# wristband-pcb.net
KiCad netlist of a schematic drawn in EAGLE
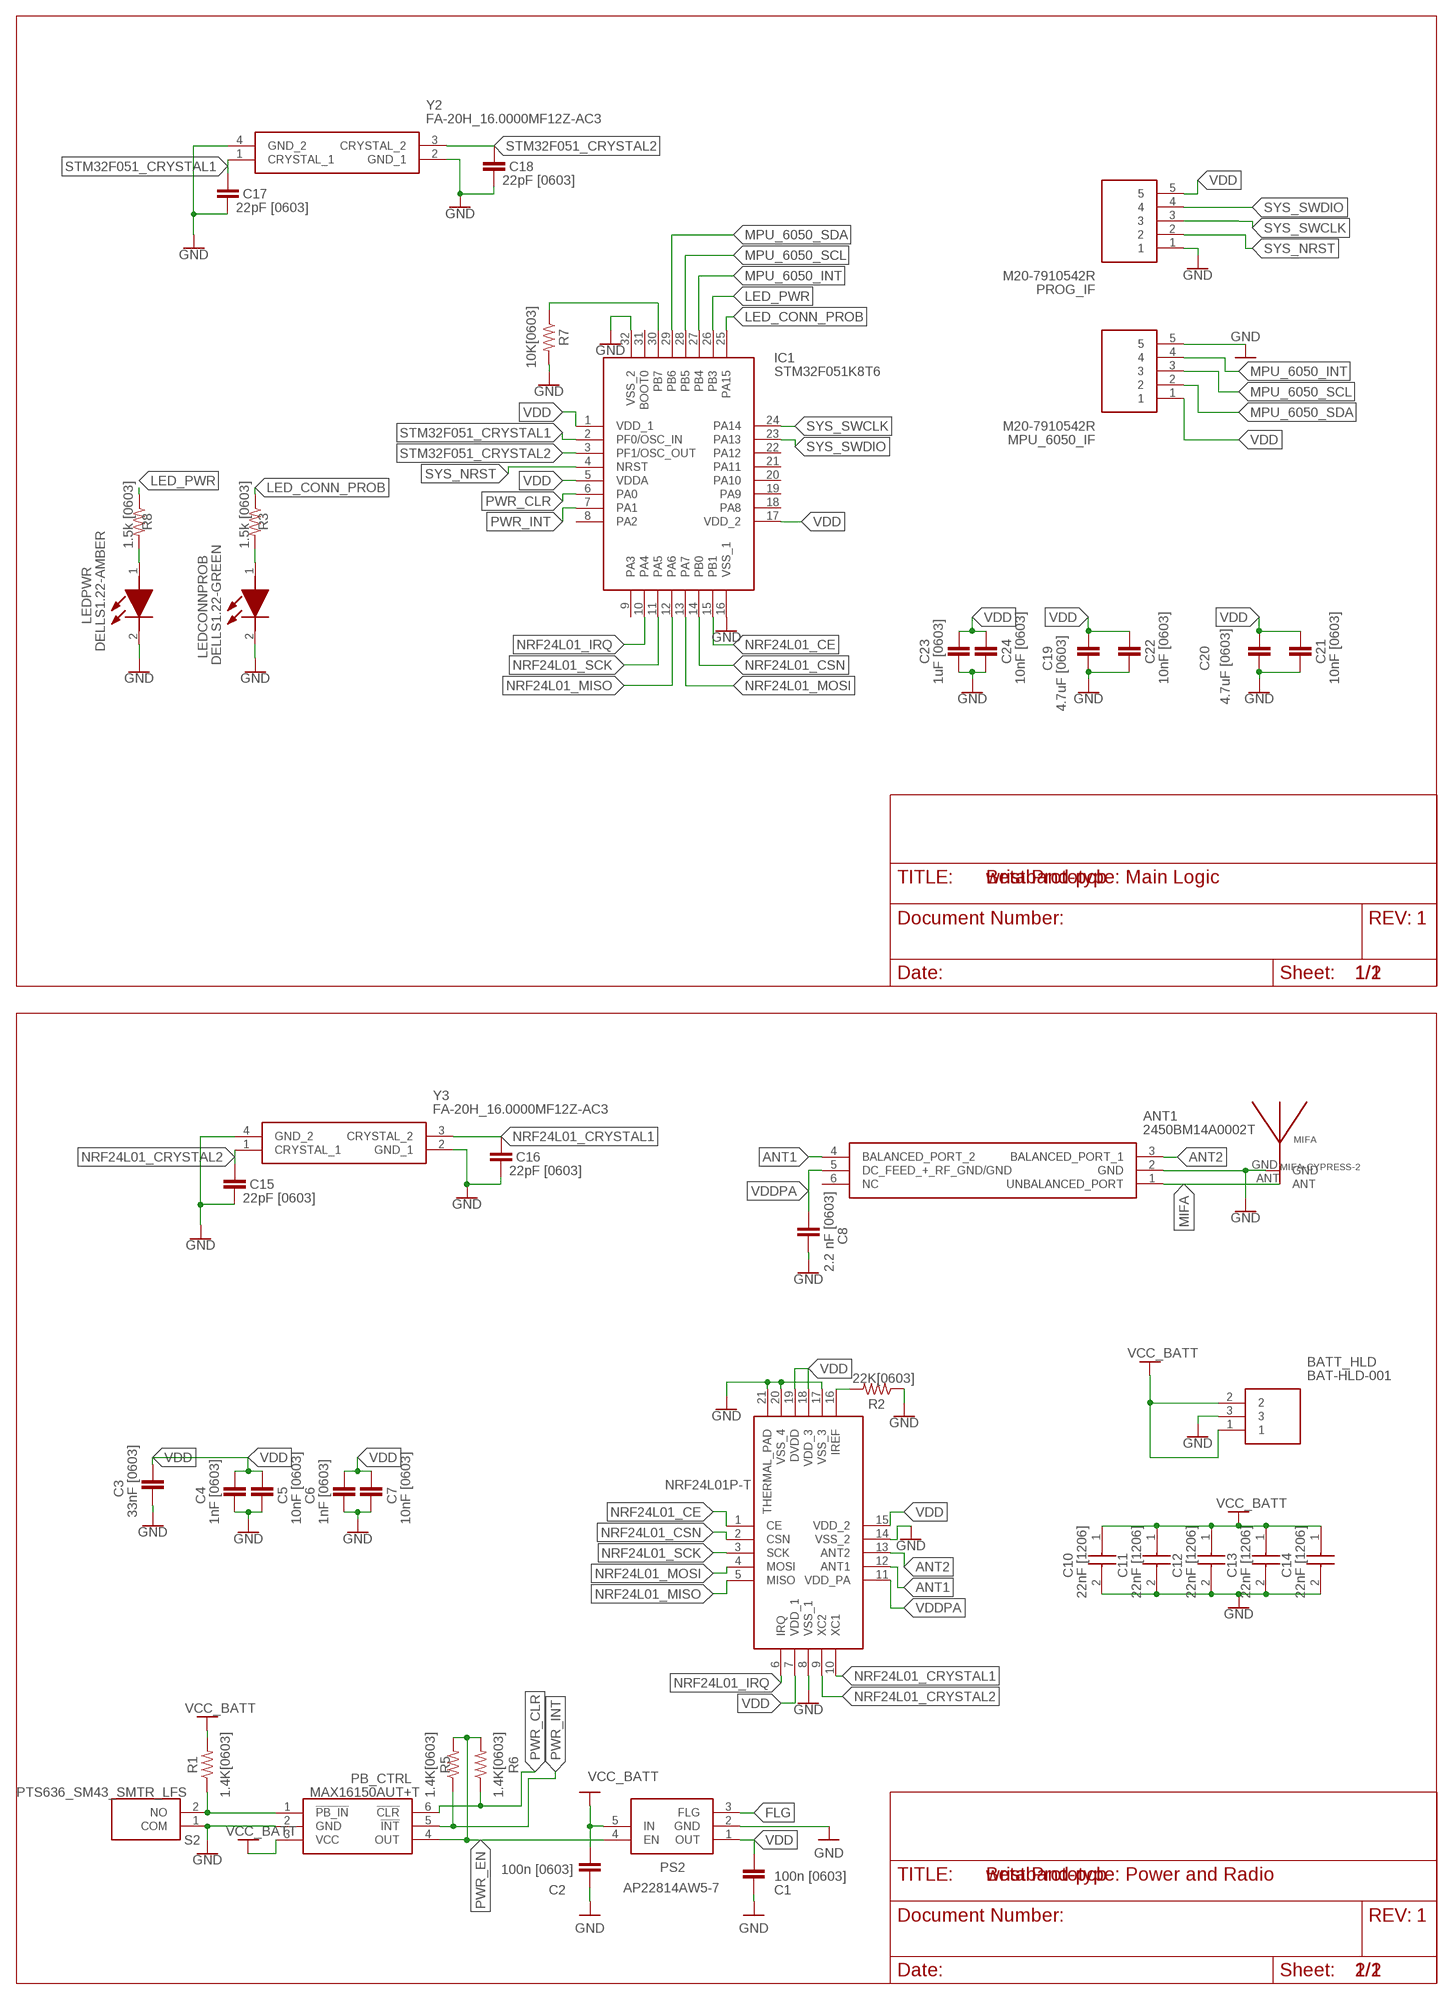
[diagram p0: schematic, sheet 1]

(export (version "E")
  (design (tool "Eeschema 10.0.6"))
  (components
    (comp (ref "ANT1")
      (value "2450BM14A0002T")
      (footprint "eagle-import:2450BM14A0002T")
      (fields (field (name "MOUSER_PART_NUMBER") "609-2450BM14A0002T"))
      (libsource (lib "eagle-import") (part "2450BM14A0002T"))
    )
    (comp (ref "BATT_HLD")
      (value "BAT-HLD-001")
      (footprint "eagle-import:BATHLD001")
      (fields (field (name "MOUSER_PART_NUMBER") "712-BAT-HLD-001"))
      (libsource (lib "eagle-import") (part "BAT-HLD-001"))
    )
    (comp (ref "C1")
      (value "100n [0603]")
      (footprint "eagle-import:CAPC1608X85")
      (libsource (lib "eagle-import") (part "CCHIP-0603(1608-METRIC)_"))
    )
    (comp (ref "C2")
      (value "100n [0603]")
      (footprint "eagle-import:CAPC1608X85")
      (libsource (lib "eagle-import") (part "CCHIP-0603(1608-METRIC)_"))
    )
    (comp (ref "C3")
      (value "33nF [0603]")
      (footprint "eagle-import:RESC0603_L")
      (libsource (lib "eagle-import") (part "CAPACITOR_0603_L"))
    )
    (comp (ref "C4")
      (value "1nF [0603]")
      (footprint "eagle-import:RESC0603_L")
      (libsource (lib "eagle-import") (part "CAPACITOR_0603_L"))
    )
    (comp (ref "C5")
      (value "10nF [0603]")
      (footprint "eagle-import:RESC0603_L")
      (libsource (lib "eagle-import") (part "CAPACITOR_0603_L"))
    )
    (comp (ref "C6")
      (value "1nF [0603]")
      (footprint "eagle-import:RESC0603_L")
      (libsource (lib "eagle-import") (part "CAPACITOR_0603_L"))
    )
    (comp (ref "C7")
      (value "10nF [0603]")
      (footprint "eagle-import:RESC0603_L")
      (libsource (lib "eagle-import") (part "CAPACITOR_0603_L"))
    )
    (comp (ref "C8")
      (value "2.2 nF [0603]")
      (footprint "eagle-import:RESC0603_L")
      (libsource (lib "eagle-import") (part "CAPACITOR_0603_L"))
    )
    (comp (ref "C10")
      (value "22nF [1206]")
      (footprint "eagle-import:CAPC3216X180N")
      (fields (field (name "MANUFACTURER_PART_NUMBER") "CL31B226KPHNNNE"))
      (libsource (lib "eagle-import") (part "CL31B226KPHNNNE"))
    )
    (comp (ref "C11")
      (value "22nF [1206]")
      (footprint "eagle-import:CAPC3216X180N")
      (fields (field (name "MANUFACTURER_PART_NUMBER") "CL31B226KPHNNNE"))
      (libsource (lib "eagle-import") (part "CL31B226KPHNNNE"))
    )
    (comp (ref "C12")
      (value "22nF [1206]")
      (footprint "eagle-import:CAPC3216X180N")
      (fields (field (name "MANUFACTURER_PART_NUMBER") "CL31B226KPHNNNE"))
      (libsource (lib "eagle-import") (part "CL31B226KPHNNNE"))
    )
    (comp (ref "C13")
      (value "22nF [1206]")
      (footprint "eagle-import:CAPC3216X180N")
      (fields (field (name "MANUFACTURER_PART_NUMBER") "CL31B226KPHNNNE"))
      (libsource (lib "eagle-import") (part "CL31B226KPHNNNE"))
    )
    (comp (ref "C14")
      (value "22nF [1206]")
      (footprint "eagle-import:CAPC3216X180N")
      (fields (field (name "MANUFACTURER_PART_NUMBER") "CL31B226KPHNNNE"))
      (libsource (lib "eagle-import") (part "CL31B226KPHNNNE"))
    )
    (comp (ref "C15")
      (value "22pF [0603]")
      (footprint "eagle-import:RESC0603_L")
      (libsource (lib "eagle-import") (part "CAPACITOR_0603_L"))
    )
    (comp (ref "C16")
      (value "22pF [0603]")
      (footprint "eagle-import:RESC0603_L")
      (libsource (lib "eagle-import") (part "CAPACITOR_0603_L"))
    )
    (comp (ref "C17")
      (value "22pF [0603]")
      (footprint "eagle-import:RESC0603_L")
      (libsource (lib "eagle-import") (part "CAPACITOR_0603_L"))
    )
    (comp (ref "C18")
      (value "22pF [0603]")
      (footprint "eagle-import:RESC0603_L")
      (libsource (lib "eagle-import") (part "CAPACITOR_0603_L"))
    )
    (comp (ref "C19")
      (value "4.7uF [0603]")
      (footprint "eagle-import:RESC0603_L")
      (libsource (lib "eagle-import") (part "CAPACITOR_0603_L"))
    )
    (comp (ref "C20")
      (value "4.7uF [0603]")
      (footprint "eagle-import:RESC0603_L")
      (libsource (lib "eagle-import") (part "CAPACITOR_0603_L"))
    )
    (comp (ref "C21")
      (value "10nF [0603]")
      (footprint "eagle-import:RESC0603_L")
      (libsource (lib "eagle-import") (part "CAPACITOR_0603_L"))
    )
    (comp (ref "C22")
      (value "10nF [0603]")
      (footprint "eagle-import:RESC0603_L")
      (libsource (lib "eagle-import") (part "CAPACITOR_0603_L"))
    )
    (comp (ref "C23")
      (value "1uF [0603]")
      (footprint "eagle-import:RESC0603_L")
      (libsource (lib "eagle-import") (part "CAPACITOR_0603_L"))
    )
    (comp (ref "C24")
      (value "10nF [0603]")
      (footprint "eagle-import:RESC0603_L")
      (libsource (lib "eagle-import") (part "CAPACITOR_0603_L"))
    )
    (comp (ref "IC1")
      (value "STM32F051K8T6")
      (footprint "eagle-import:QFP80P900X900X160-32N")
      (fields (field (name "MOUSER_PART_NUMBER") "511-STM32F051K8T6"))
      (libsource (lib "eagle-import") (part "STM32F051K8T6"))
    )
    (comp (ref "LEDCONNPROB")
      (value "DELLS1.22-GREEN")
      (footprint "eagle-import:KSDELLS122JHKI1")
      (fields
        (field (name "MANUFACTURER_PART_NUMBER") "KS DELLS1.22-JHKI-1")
        (field (name "MOUSER_PART_NUMBER") "720-KSDELLS122A4852")
      )
      (libsource (lib "eagle-import") (part "KS_DELLS1.22-JHKI-1"))
    )
    (comp (ref "LEDPWR")
      (value "DELLS1.22-AMBER")
      (footprint "eagle-import:KSDELLS122JHKI1")
      (fields
        (field (name "MANUFACTURER_PART_NUMBER") "KS DELLS1.22-JHKI-1")
        (field (name "MOUSER_PART_NUMBER") "720-KSDELLS122A4852")
      )
      (libsource (lib "eagle-import") (part "KS_DELLS1.22-JHKI-1"))
    )
    (comp (ref "MIFA")
      (value "MIFA-CYPRESS-2")
      (footprint "eagle-import:MIFA-CYPRESS-2")
      (libsource (lib "eagle-import") (part "MIFA-CYPRESS-2"))
    )
    (comp (ref "MPU_6050_IF")
      (value "M20-7910542R")
      (footprint "eagle-import:M207910542R")
      (fields (field (name "MOUSER_PART_NUMBER") "855-M20-7910542R"))
      (libsource (lib "eagle-import") (part "M20-7910542R"))
    )
    (comp (ref "NRF24L01+")
      (value "NRF24L01P-T")
      (footprint "eagle-import:QFN50P400X400X95-21N")
      (fields
        (field (name "MANUFACTURER_PART_NUMBER") "nRF24L01P-T")
        (field (name "MOUSER_PART_NUMBER") "949-NRF24L01P-T")
      )
      (libsource (lib "eagle-import") (part "NRF24L01P-T"))
    )
    (comp (ref "PB_CTRL")
      (value "MAX16150AUT+T")
      (footprint "eagle-import:SOT95P280X145-6N")
      (fields (field (name "MOUSER_PART_NUMBER") "700-MAX16150AUT+T"))
      (libsource (lib "eagle-import") (part "MAX16150AUT+T"))
    )
    (comp (ref "PROG_IF")
      (value "M20-7910542R")
      (footprint "eagle-import:M207910542R")
      (fields (field (name "MOUSER_PART_NUMBER") "855-M20-7910542R"))
      (libsource (lib "eagle-import") (part "M20-7910542R"))
    )
    (comp (ref "PS2")
      (value "AP22814AW5-7")
      (footprint "eagle-import:SOT95P285X130-5N")
      (fields (field (name "MOUSER_PART_NUMBER") "621-AP22814AW5-7"))
      (libsource (lib "eagle-import") (part "AP22814AW5-7"))
    )
    (comp (ref "R1")
      (value "1.4K[0603]")
      (footprint "eagle-import:RESC1608X60")
      (libsource (lib "eagle-import") (part "R-USCHIP-0603(1608-METRIC)_"))
    )
    (comp (ref "R2")
      (value "22K[0603]")
      (footprint "eagle-import:RESC1608X60")
      (libsource (lib "eagle-import") (part "R-USCHIP-0603(1608-METRIC)_"))
    )
    (comp (ref "R3")
      (value "1.5k [0603]")
      (footprint "eagle-import:RESC1608X60")
      (libsource (lib "eagle-import") (part "R-USCHIP-0603(1608-METRIC)_"))
    )
    (comp (ref "R5")
      (value "1.4K[0603]")
      (footprint "eagle-import:RESC1608X60")
      (libsource (lib "eagle-import") (part "R-USCHIP-0603(1608-METRIC)_"))
    )
    (comp (ref "R6")
      (value "1.4K[0603]")
      (footprint "eagle-import:RESC1608X60")
      (libsource (lib "eagle-import") (part "R-USCHIP-0603(1608-METRIC)_"))
    )
    (comp (ref "R7")
      (value "10K[0603]")
      (footprint "eagle-import:RESC1608X60")
      (libsource (lib "eagle-import") (part "R-USCHIP-0603(1608-METRIC)_"))
    )
    (comp (ref "R8")
      (value "1.5k [0603]")
      (footprint "eagle-import:RESC1608X60")
      (libsource (lib "eagle-import") (part "R-USCHIP-0603(1608-METRIC)_"))
    )
    (comp (ref "S2")
      (value "PTS636_SM43_SMTR_LFS")
      (footprint "eagle-import:PTS636SM43SMTRLFS")
      (fields
        (field (name "MANUFACTURER_PART_NUMBER") "PTS636 SM43 SMTR LFS")
        (field (name "MOUSER_PART_NUMBER") "611-PTS636SM43SMTRLF")
      )
      (libsource (lib "eagle-import") (part "PTS636_SM43_SMTR_LFS"))
    )
    (comp (ref "Y2")
      (value "FA-20H_16.0000MF12Z-AC3")
      (footprint "eagle-import:FA20H160000MF12ZAC3")
      (fields
        (field (name "MANUFACTURER_PART_NUMBER") "FA-20H 16.0000MF12Z-AC3")
        (field (name "MOUSER_PART_NUMBER") "732-FA20H-16F12Z-AC3")
      )
      (libsource (lib "eagle-import") (part "FA-20H_16.0000MF12Z-AC3"))
    )
    (comp (ref "Y3")
      (value "FA-20H_16.0000MF12Z-AC3")
      (footprint "eagle-import:FA20H160000MF12ZAC3")
      (fields
        (field (name "MANUFACTURER_PART_NUMBER") "FA-20H 16.0000MF12Z-AC3")
        (field (name "MOUSER_PART_NUMBER") "732-FA20H-16F12Z-AC3")
      )
      (libsource (lib "eagle-import") (part "FA-20H_16.0000MF12Z-AC3"))
    )
  )
  (nets
    (net (code "1") (name "ANT1") (class "Default")
      (node (ref "ANT1") (pin "4") (pinfunction "BALANCED_PORT_2_4") (pintype "bidirectional"))
      (node (ref "NRF24L01+") (pin "12") (pinfunction "ANT1_12") (pintype "bidirectional"))
    )
    (net (code "2") (name "ANT2") (class "Default")
      (node (ref "ANT1") (pin "3") (pinfunction "BALANCED_PORT_1_3") (pintype "bidirectional"))
      (node (ref "NRF24L01+") (pin "13") (pinfunction "ANT2_13") (pintype "bidirectional"))
    )
    (net (code "3") (name "FLG") (class "Default")
      (node (ref "PS2") (pin "3") (pinfunction "FLG_3") (pintype "bidirectional"))
    )
    (net (code "4") (name "GND") (class "Default")
      (node (ref "ANT1") (pin "2") (pinfunction "GND_2") (pintype "bidirectional"))
      (node (ref "BATT_HLD") (pin "3") (pinfunction "3_3") (pintype "bidirectional"))
      (node (ref "C1") (pin "2") (pinfunction "2_2") (pintype "passive"))
      (node (ref "C10") (pin "2") (pinfunction "2_2") (pintype "bidirectional"))
      (node (ref "C11") (pin "2") (pinfunction "2_2") (pintype "bidirectional"))
      (node (ref "C12") (pin "2") (pinfunction "2_2") (pintype "bidirectional"))
      (node (ref "C13") (pin "2") (pinfunction "2_2") (pintype "bidirectional"))
      (node (ref "C14") (pin "2") (pinfunction "2_2") (pintype "bidirectional"))
      (node (ref "C15") (pin "2") (pinfunction "2_2") (pintype "passive"))
      (node (ref "C16") (pin "2") (pinfunction "2_2") (pintype "passive"))
      (node (ref "C17") (pin "2") (pinfunction "2_2") (pintype "passive"))
      (node (ref "C18") (pin "2") (pinfunction "2_2") (pintype "passive"))
      (node (ref "C19") (pin "2") (pinfunction "2_2") (pintype "passive"))
      (node (ref "C2") (pin "2") (pinfunction "2_2") (pintype "passive"))
      (node (ref "C20") (pin "2") (pinfunction "2_2") (pintype "passive"))
      (node (ref "C21") (pin "2") (pinfunction "2_2") (pintype "passive"))
      (node (ref "C22") (pin "2") (pinfunction "2_2") (pintype "passive"))
      (node (ref "C23") (pin "2") (pinfunction "2_2") (pintype "passive"))
      (node (ref "C24") (pin "2") (pinfunction "2_2") (pintype "passive"))
      (node (ref "C3") (pin "2") (pinfunction "2_2") (pintype "passive"))
      (node (ref "C4") (pin "2") (pinfunction "2_2") (pintype "passive"))
      (node (ref "C5") (pin "2") (pinfunction "2_2") (pintype "passive"))
      (node (ref "C6") (pin "2") (pinfunction "2_2") (pintype "passive"))
      (node (ref "C7") (pin "2") (pinfunction "2_2") (pintype "passive"))
      (node (ref "C8") (pin "2") (pinfunction "2_2") (pintype "passive"))
      (node (ref "IC1") (pin "16") (pinfunction "VSS_1_16") (pintype "power_in"))
      (node (ref "IC1") (pin "32") (pinfunction "VSS_2_32") (pintype "power_in"))
      (node (ref "LEDCONNPROB") (pin "2") (pinfunction "K_2") (pintype "bidirectional"))
      (node (ref "LEDPWR") (pin "2") (pinfunction "K_2") (pintype "bidirectional"))
      (node (ref "MIFA") (pin "GND") (pinfunction "GND_GND") (pintype "bidirectional"))
      (node (ref "MPU_6050_IF") (pin "5") (pinfunction "5_5") (pintype "bidirectional"))
      (node (ref "NRF24L01+") (pin "14") (pinfunction "VSS_2_14") (pintype "bidirectional"))
      (node (ref "NRF24L01+") (pin "17") (pinfunction "VSS_3_17") (pintype "bidirectional"))
      (node (ref "NRF24L01+") (pin "20") (pinfunction "VSS_4_20") (pintype "bidirectional"))
      (node (ref "NRF24L01+") (pin "21") (pinfunction "THERMAL_PAD_21") (pintype "bidirectional"))
      (node (ref "NRF24L01+") (pin "8") (pinfunction "VSS_1_8") (pintype "bidirectional"))
      (node (ref "PB_CTRL") (pin "2") (pinfunction "GND_2") (pintype "bidirectional"))
      (node (ref "PROG_IF") (pin "1") (pinfunction "1_1") (pintype "bidirectional"))
      (node (ref "PS2") (pin "2") (pinfunction "GND_2") (pintype "power_in"))
      (node (ref "R2") (pin "1") (pinfunction "1_1") (pintype "passive"))
      (node (ref "R7") (pin "2") (pinfunction "2_2") (pintype "passive"))
      (node (ref "S2") (pin "1") (pinfunction "COM_1") (pintype "bidirectional"))
      (node (ref "Y2") (pin "2") (pinfunction "GND_1_2") (pintype "bidirectional"))
      (node (ref "Y2") (pin "4") (pinfunction "GND_2_4") (pintype "bidirectional"))
      (node (ref "Y3") (pin "2") (pinfunction "GND_1_2") (pintype "bidirectional"))
      (node (ref "Y3") (pin "4") (pinfunction "GND_2_4") (pintype "bidirectional"))
    )
    (net (code "5") (name "LED_CONN_PROB") (class "Default")
      (node (ref "IC1") (pin "25") (pinfunction "PA15_25") (pintype "bidirectional"))
      (node (ref "R3") (pin "1") (pinfunction "1_1") (pintype "passive"))
    )
    (net (code "6") (name "LED_PWR") (class "Default")
      (node (ref "IC1") (pin "26") (pinfunction "PB3_26") (pintype "bidirectional"))
      (node (ref "R8") (pin "1") (pinfunction "1_1") (pintype "passive"))
    )
    (net (code "7") (name "MIFA") (class "Default")
      (node (ref "ANT1") (pin "1") (pinfunction "UNBALANCED_PORT_1") (pintype "bidirectional"))
      (node (ref "MIFA") (pin "ANT") (pinfunction "ANT_ANT") (pintype "bidirectional"))
    )
    (net (code "8") (name "MPU_6050_INT") (class "Default")
      (node (ref "IC1") (pin "27") (pinfunction "PB4_27") (pintype "bidirectional"))
      (node (ref "MPU_6050_IF") (pin "4") (pinfunction "4_4") (pintype "bidirectional"))
    )
    (net (code "9") (name "MPU_6050_SCL") (class "Default")
      (node (ref "IC1") (pin "28") (pinfunction "PB5_28") (pintype "bidirectional"))
      (node (ref "MPU_6050_IF") (pin "3") (pinfunction "3_3") (pintype "bidirectional"))
    )
    (net (code "10") (name "MPU_6050_SDA") (class "Default")
      (node (ref "IC1") (pin "29") (pinfunction "PB6_29") (pintype "bidirectional"))
      (node (ref "MPU_6050_IF") (pin "2") (pinfunction "2_2") (pintype "bidirectional"))
    )
    (net (code "11") (name "NRF24L01_CE") (class "Default")
      (node (ref "IC1") (pin "15") (pinfunction "PB1_15") (pintype "bidirectional"))
      (node (ref "NRF24L01+") (pin "1") (pinfunction "CE_1") (pintype "bidirectional"))
    )
    (net (code "12") (name "NRF24L01_CRYSTAL1") (class "Default")
      (node (ref "C16") (pin "1") (pinfunction "1_1") (pintype "passive"))
      (node (ref "NRF24L01+") (pin "10") (pinfunction "XC1_10") (pintype "bidirectional"))
      (node (ref "Y3") (pin "3") (pinfunction "CRYSTAL_2_3") (pintype "bidirectional"))
    )
    (net (code "13") (name "NRF24L01_CRYSTAL2") (class "Default")
      (node (ref "C15") (pin "1") (pinfunction "1_1") (pintype "passive"))
      (node (ref "NRF24L01+") (pin "9") (pinfunction "XC2_9") (pintype "bidirectional"))
      (node (ref "Y3") (pin "1") (pinfunction "CRYSTAL_1_1") (pintype "bidirectional"))
    )
    (net (code "14") (name "NRF24L01_CSN") (class "Default")
      (node (ref "IC1") (pin "14") (pinfunction "PB0_14") (pintype "bidirectional"))
      (node (ref "NRF24L01+") (pin "2") (pinfunction "CSN_2") (pintype "bidirectional"))
    )
    (net (code "15") (name "NRF24L01_IRQ") (class "Default")
      (node (ref "IC1") (pin "10") (pinfunction "PA4_10") (pintype "bidirectional"))
      (node (ref "NRF24L01+") (pin "6") (pinfunction "IRQ_6") (pintype "bidirectional"))
    )
    (net (code "16") (name "NRF24L01_MISO") (class "Default")
      (node (ref "IC1") (pin "12") (pinfunction "PA6_12") (pintype "bidirectional"))
      (node (ref "NRF24L01+") (pin "5") (pinfunction "MISO_5") (pintype "bidirectional"))
    )
    (net (code "17") (name "NRF24L01_MOSI") (class "Default")
      (node (ref "IC1") (pin "13") (pinfunction "PA7_13") (pintype "bidirectional"))
      (node (ref "NRF24L01+") (pin "4") (pinfunction "MOSI_4") (pintype "bidirectional"))
    )
    (net (code "18") (name "NRF24L01_SCK") (class "Default")
      (node (ref "IC1") (pin "11") (pinfunction "PA5_11") (pintype "bidirectional"))
      (node (ref "NRF24L01+") (pin "3") (pinfunction "SCK_3") (pintype "bidirectional"))
    )
    (net (code "19") (name "Net-(IC1-PB7)") (class "Default")
      (node (ref "IC1") (pin "30") (pinfunction "PB7_30") (pintype "bidirectional"))
      (node (ref "R7") (pin "1") (pinfunction "1_1") (pintype "passive"))
    )
    (net (code "20") (name "Net-(LEDCONNPROB-A)") (class "Default")
      (node (ref "LEDCONNPROB") (pin "1") (pinfunction "A_1") (pintype "bidirectional"))
      (node (ref "R3") (pin "2") (pinfunction "2_2") (pintype "passive"))
    )
    (net (code "21") (name "Net-(LEDPWR-A)") (class "Default")
      (node (ref "LEDPWR") (pin "1") (pinfunction "A_1") (pintype "bidirectional"))
      (node (ref "R8") (pin "2") (pinfunction "2_2") (pintype "passive"))
    )
    (net (code "22") (name "Net-(NRF24L01+-IREF)") (class "Default")
      (node (ref "NRF24L01+") (pin "16") (pinfunction "IREF_16") (pintype "bidirectional"))
      (node (ref "R2") (pin "2") (pinfunction "2_2") (pintype "passive"))
    )
    (net (code "23") (name "Net-(PB_CTRL-~{PB_IN})") (class "Default")
      (node (ref "PB_CTRL") (pin "1") (pinfunction "~{PB_IN}_1") (pintype "bidirectional"))
      (node (ref "R1") (pin "1") (pinfunction "1_1") (pintype "passive"))
      (node (ref "S2") (pin "2") (pinfunction "NO_2") (pintype "bidirectional"))
    )
    (net (code "24") (name "PWR_CLR") (class "Default")
      (node (ref "IC1") (pin "6") (pinfunction "PA0_6") (pintype "bidirectional"))
      (node (ref "PB_CTRL") (pin "6") (pinfunction "~{CLR}_6") (pintype "bidirectional"))
      (node (ref "R6") (pin "1") (pinfunction "1_1") (pintype "passive"))
    )
    (net (code "25") (name "PWR_EN") (class "Default")
      (node (ref "PB_CTRL") (pin "4") (pinfunction "OUT_4") (pintype "bidirectional"))
      (node (ref "PS2") (pin "4") (pinfunction "EN_4") (pintype "input"))
      (node (ref "R5") (pin "2") (pinfunction "2_2") (pintype "passive"))
      (node (ref "R6") (pin "2") (pinfunction "2_2") (pintype "passive"))
    )
    (net (code "26") (name "PWR_INT") (class "Default")
      (node (ref "IC1") (pin "7") (pinfunction "PA1_7") (pintype "bidirectional"))
      (node (ref "PB_CTRL") (pin "5") (pinfunction "~{INT}_5") (pintype "bidirectional"))
      (node (ref "R5") (pin "1") (pinfunction "1_1") (pintype "passive"))
    )
    (net (code "27") (name "STM32F051_CRYSTAL1") (class "Default")
      (node (ref "C17") (pin "1") (pinfunction "1_1") (pintype "passive"))
      (node (ref "IC1") (pin "2") (pinfunction "PF0/OSC_IN_2") (pintype "input"))
      (node (ref "Y2") (pin "1") (pinfunction "CRYSTAL_1_1") (pintype "bidirectional"))
    )
    (net (code "28") (name "STM32F051_CRYSTAL2") (class "Default")
      (node (ref "C18") (pin "1") (pinfunction "1_1") (pintype "passive"))
      (node (ref "IC1") (pin "3") (pinfunction "PF1/OSC_OUT_3") (pintype "output"))
      (node (ref "Y2") (pin "3") (pinfunction "CRYSTAL_2_3") (pintype "bidirectional"))
    )
    (net (code "29") (name "SYS_NRST") (class "Default")
      (node (ref "IC1") (pin "4") (pinfunction "NRST_4") (pintype "input"))
      (node (ref "PROG_IF") (pin "2") (pinfunction "2_2") (pintype "bidirectional"))
    )
    (net (code "30") (name "SYS_SWCLK") (class "Default")
      (node (ref "IC1") (pin "24") (pinfunction "PA14_24") (pintype "bidirectional"))
      (node (ref "PROG_IF") (pin "3") (pinfunction "3_3") (pintype "bidirectional"))
    )
    (net (code "31") (name "SYS_SWDIO") (class "Default")
      (node (ref "IC1") (pin "23") (pinfunction "PA13_23") (pintype "bidirectional"))
      (node (ref "PROG_IF") (pin "4") (pinfunction "4_4") (pintype "bidirectional"))
    )
    (net (code "32") (name "VCC_BATT") (class "Default")
      (node (ref "BATT_HLD") (pin "1") (pinfunction "1_1") (pintype "bidirectional"))
      (node (ref "BATT_HLD") (pin "2") (pinfunction "2_2") (pintype "bidirectional"))
      (node (ref "C10") (pin "1") (pinfunction "1_1") (pintype "bidirectional"))
      (node (ref "C11") (pin "1") (pinfunction "1_1") (pintype "bidirectional"))
      (node (ref "C12") (pin "1") (pinfunction "1_1") (pintype "bidirectional"))
      (node (ref "C13") (pin "1") (pinfunction "1_1") (pintype "bidirectional"))
      (node (ref "C14") (pin "1") (pinfunction "1_1") (pintype "bidirectional"))
      (node (ref "C2") (pin "1") (pinfunction "1_1") (pintype "passive"))
      (node (ref "PB_CTRL") (pin "3") (pinfunction "VCC_3") (pintype "bidirectional"))
      (node (ref "PS2") (pin "5") (pinfunction "IN_5") (pintype "power_in"))
      (node (ref "R1") (pin "2") (pinfunction "2_2") (pintype "passive"))
    )
    (net (code "33") (name "VDD") (class "Default")
      (node (ref "C1") (pin "1") (pinfunction "1_1") (pintype "passive"))
      (node (ref "C19") (pin "1") (pinfunction "1_1") (pintype "passive"))
      (node (ref "C20") (pin "1") (pinfunction "1_1") (pintype "passive"))
      (node (ref "C21") (pin "1") (pinfunction "1_1") (pintype "passive"))
      (node (ref "C22") (pin "1") (pinfunction "1_1") (pintype "passive"))
      (node (ref "C23") (pin "1") (pinfunction "1_1") (pintype "passive"))
      (node (ref "C24") (pin "1") (pinfunction "1_1") (pintype "passive"))
      (node (ref "C3") (pin "1") (pinfunction "1_1") (pintype "passive"))
      (node (ref "C4") (pin "1") (pinfunction "1_1") (pintype "passive"))
      (node (ref "C5") (pin "1") (pinfunction "1_1") (pintype "passive"))
      (node (ref "C6") (pin "1") (pinfunction "1_1") (pintype "passive"))
      (node (ref "C7") (pin "1") (pinfunction "1_1") (pintype "passive"))
      (node (ref "IC1") (pin "1") (pinfunction "VDD_1_1") (pintype "power_in"))
      (node (ref "IC1") (pin "17") (pinfunction "VDD_2_17") (pintype "power_in"))
      (node (ref "IC1") (pin "5") (pinfunction "VDDA_5") (pintype "power_in"))
      (node (ref "MPU_6050_IF") (pin "1") (pinfunction "1_1") (pintype "bidirectional"))
      (node (ref "NRF24L01+") (pin "15") (pinfunction "VDD_2_15") (pintype "bidirectional"))
      (node (ref "NRF24L01+") (pin "18") (pinfunction "VDD_3_18") (pintype "bidirectional"))
      (node (ref "NRF24L01+") (pin "19") (pinfunction "DVDD_19") (pintype "bidirectional"))
      (node (ref "NRF24L01+") (pin "7") (pinfunction "VDD_1_7") (pintype "bidirectional"))
      (node (ref "PROG_IF") (pin "5") (pinfunction "5_5") (pintype "bidirectional"))
      (node (ref "PS2") (pin "1") (pinfunction "OUT_1") (pintype "power_in"))
    )
    (net (code "34") (name "VDDPA") (class "Default")
      (node (ref "ANT1") (pin "5") (pinfunction "DC_FEED_+_RF_GND/GND_5") (pintype "bidirectional"))
      (node (ref "C8") (pin "1") (pinfunction "1_1") (pintype "passive"))
      (node (ref "NRF24L01+") (pin "11") (pinfunction "VDD_PA_11") (pintype "bidirectional"))
    )
    (net (code "35") (name "unconnected-(ANT1-NC-Pad6)") (class "Default")
      (node (ref "ANT1") (pin "6") (pinfunction "NC_6") (pintype "no_connect"))
    )
    (net (code "36") (name "unconnected-(IC1-BOOT0-Pad31)") (class "Default")
      (node (ref "IC1") (pin "31") (pinfunction "BOOT0_31") (pintype "bidirectional"))
    )
    (net (code "37") (name "unconnected-(IC1-PA2-Pad8)") (class "Default")
      (node (ref "IC1") (pin "8") (pinfunction "PA2_8") (pintype "bidirectional"))
    )
    (net (code "38") (name "unconnected-(IC1-PA3-Pad9)") (class "Default")
      (node (ref "IC1") (pin "9") (pinfunction "PA3_9") (pintype "bidirectional"))
    )
    (net (code "39") (name "unconnected-(IC1-PA8-Pad18)") (class "Default")
      (node (ref "IC1") (pin "18") (pinfunction "PA8_18") (pintype "bidirectional"))
    )
    (net (code "40") (name "unconnected-(IC1-PA9-Pad19)") (class "Default")
      (node (ref "IC1") (pin "19") (pinfunction "PA9_19") (pintype "bidirectional"))
    )
    (net (code "41") (name "unconnected-(IC1-PA10-Pad20)") (class "Default")
      (node (ref "IC1") (pin "20") (pinfunction "PA10_20") (pintype "bidirectional"))
    )
    (net (code "42") (name "unconnected-(IC1-PA11-Pad21)") (class "Default")
      (node (ref "IC1") (pin "21") (pinfunction "PA11_21") (pintype "bidirectional"))
    )
    (net (code "43") (name "unconnected-(IC1-PA12-Pad22)") (class "Default")
      (node (ref "IC1") (pin "22") (pinfunction "PA12_22") (pintype "bidirectional"))
    )
  )
)
